# nahhhhh.net
KiCad netlist of a schematic drawn in EAGLE
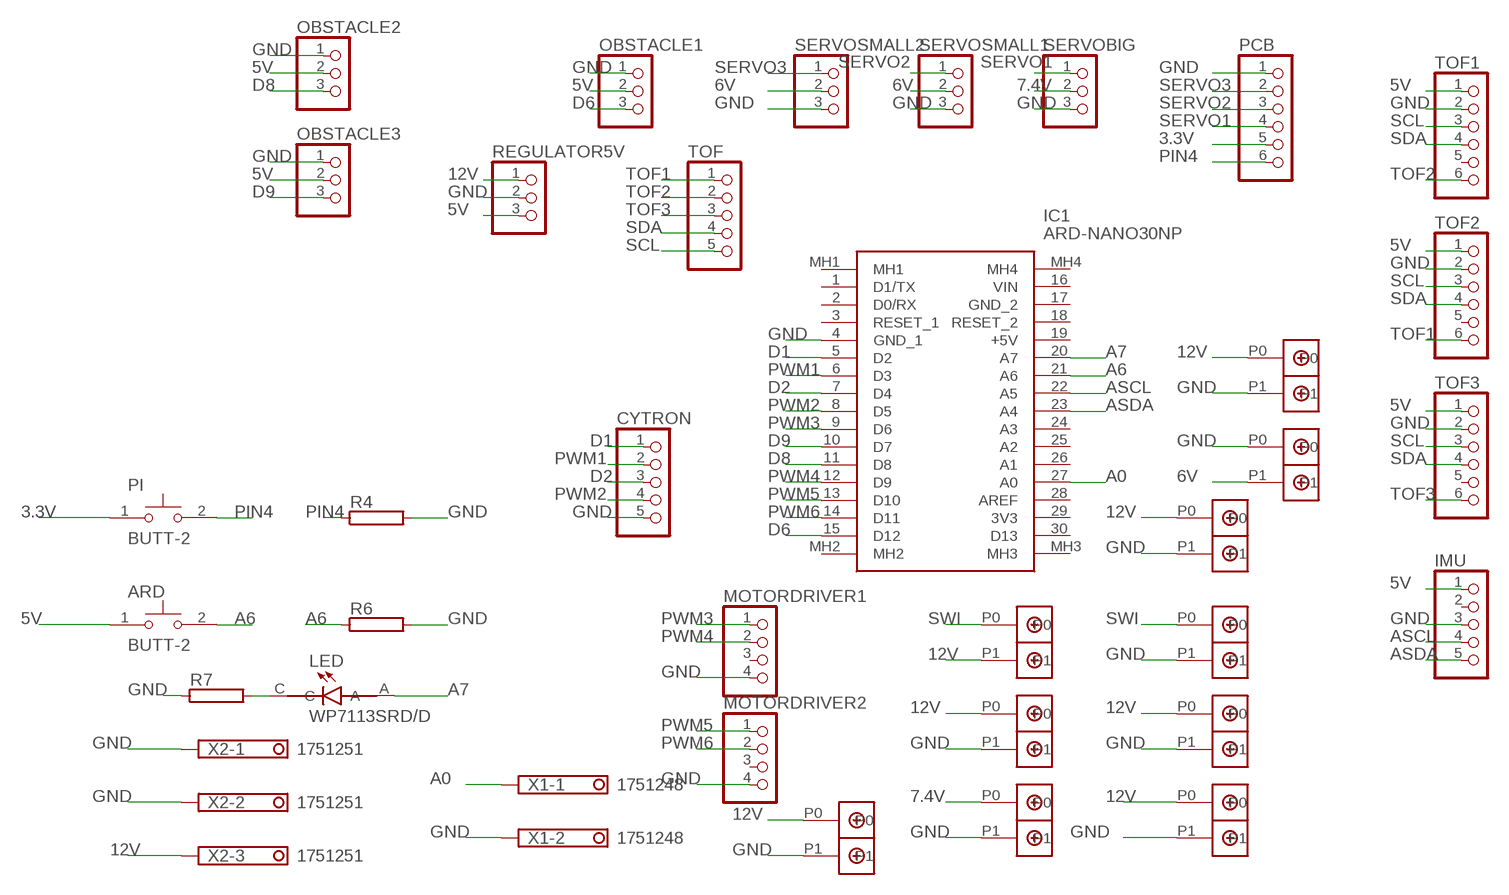
[diagram p0: schematic, sheet 1]

(export (version "E")
  (design (tool "Eeschema 10.0.6"))
  (components
    (comp (ref "ARD")
      (value "BUTT-2")
      (footprint "eagle-import:SW_BUTT-2")
      (fields (field (name "MF") "Gravitech"))
      (libsource (lib "eagle-import") (part "BUTT-2"))
    )
    (comp (ref "BATERY")
      (value "DBCONN-1X2")
      (footprint "eagle-import:DBCONN-1X2")
      (libsource (lib "eagle-import") (part "DBCONN-1X2"))
    )
    (comp (ref "BUCKSERVO")
      (value "DBCONN-1X2")
      (footprint "eagle-import:DBCONN-1X2")
      (libsource (lib "eagle-import") (part "DBCONN-1X2"))
    )
    (comp (ref "CYTRON")
      (value "PINHD-1X5")
      (footprint "eagle-import:1X05")
      (libsource (lib "eagle-import") (part "PINHD-1X5"))
    )
    (comp (ref "CYTRONPOWER")
      (value "DBCONN-1X2")
      (footprint "eagle-import:DBCONN-1X2")
      (libsource (lib "eagle-import") (part "DBCONN-1X2"))
    )
    (comp (ref "IC1")
      (value "ARD-NANO30NP")
      (footprint "eagle-import:ARDNANO30NP")
      (fields (field (name "MOUSER_PART_NUMBER") "992-ARD-NANO30NP"))
      (libsource (lib "eagle-import") (part "ARD-NANO30NP"))
    )
    (comp (ref "IMU")
      (value "PINHD-1X5")
      (footprint "eagle-import:1X05")
      (libsource (lib "eagle-import") (part "PINHD-1X5"))
    )
    (comp (ref "LED")
      (value "WP7113SRD/D")
      (footprint "eagle-import:LED_WP7113SRD_D")
      (fields (field (name "MF") "Kingbright"))
      (libsource (lib "eagle-import") (part "WP7113SRD/D"))
    )
    (comp (ref "LEDS")
      (value "DBCONN-1X2")
      (footprint "eagle-import:DBCONN-1X2")
      (libsource (lib "eagle-import") (part "DBCONN-1X2"))
    )
    (comp (ref "LEDS1")
      (value "DBCONN-1X2")
      (footprint "eagle-import:DBCONN-1X2")
      (libsource (lib "eagle-import") (part "DBCONN-1X2"))
    )
    (comp (ref "LEDS2")
      (value "DBCONN-1X2")
      (footprint "eagle-import:DBCONN-1X2")
      (libsource (lib "eagle-import") (part "DBCONN-1X2"))
    )
    (comp (ref "LEDS3")
      (value "DBCONN-1X2")
      (footprint "eagle-import:DBCONN-1X2")
      (libsource (lib "eagle-import") (part "DBCONN-1X2"))
    )
    (comp (ref "LEDS4")
      (value "DBCONN-1X2")
      (footprint "eagle-import:DBCONN-1X2")
      (libsource (lib "eagle-import") (part "DBCONN-1X2"))
    )
    (comp (ref "LEDS5")
      (value "DBCONN-1X2")
      (footprint "eagle-import:DBCONN-1X2")
      (libsource (lib "eagle-import") (part "DBCONN-1X2"))
    )
    (comp (ref "MOTORDRIVER1")
      (value "PINHD-1X4")
      (footprint "eagle-import:1X04")
      (libsource (lib "eagle-import") (part "PINHD-1X4"))
    )
    (comp (ref "MOTORDRIVER2")
      (value "PINHD-1X4")
      (footprint "eagle-import:1X04")
      (libsource (lib "eagle-import") (part "PINHD-1X4"))
    )
    (comp (ref "OBSTACLE1")
      (value "PINHD-1X3")
      (footprint "eagle-import:1X03")
      (libsource (lib "eagle-import") (part "PINHD-1X3"))
    )
    (comp (ref "OBSTACLE2")
      (value "PINHD-1X3")
      (footprint "eagle-import:1X03")
      (libsource (lib "eagle-import") (part "PINHD-1X3"))
    )
    (comp (ref "OBSTACLE3")
      (value "PINHD-1X3")
      (footprint "eagle-import:1X03")
      (libsource (lib "eagle-import") (part "PINHD-1X3"))
    )
    (comp (ref "PCB")
      (value "PINHD-1X6")
      (footprint "eagle-import:1X06")
      (libsource (lib "eagle-import") (part "PINHD-1X6"))
    )
    (comp (ref "PI")
      (value "BUTT-2")
      (footprint "eagle-import:SW_BUTT-2")
      (fields (field (name "MF") "Gravitech"))
      (libsource (lib "eagle-import") (part "BUTT-2"))
    )
    (comp (ref "R4")
      (value "RHPS58")
      (footprint "eagle-import:HPS58")
      (libsource (lib "eagle-import") (part "RHPS58"))
    )
    (comp (ref "R6")
      (value "RHPS58")
      (footprint "eagle-import:HPS58")
      (libsource (lib "eagle-import") (part "RHPS58"))
    )
    (comp (ref "R7")
      (value "RHPS58")
      (footprint "eagle-import:HPS58")
      (libsource (lib "eagle-import") (part "RHPS58"))
    )
    (comp (ref "REGULATOR5V")
      (value "PINHD-1X3")
      (footprint "eagle-import:1X03")
      (libsource (lib "eagle-import") (part "PINHD-1X3"))
    )
    (comp (ref "SERVOBIG")
      (value "PINHD-1X3")
      (footprint "eagle-import:1X03")
      (libsource (lib "eagle-import") (part "PINHD-1X3"))
    )
    (comp (ref "SERVOSMALL1")
      (value "PINHD-1X3")
      (footprint "eagle-import:1X03")
      (libsource (lib "eagle-import") (part "PINHD-1X3"))
    )
    (comp (ref "SERVOSMALL2")
      (value "PINHD-1X3")
      (footprint "eagle-import:1X03")
      (libsource (lib "eagle-import") (part "PINHD-1X3"))
    )
    (comp (ref "TOF")
      (value "PINHD-1X5")
      (footprint "eagle-import:1X05")
      (libsource (lib "eagle-import") (part "PINHD-1X5"))
    )
    (comp (ref "TOF1")
      (value "PINHD-1X6")
      (footprint "eagle-import:1X06")
      (libsource (lib "eagle-import") (part "PINHD-1X6"))
    )
    (comp (ref "TOF2")
      (value "PINHD-1X6")
      (footprint "eagle-import:1X06")
      (libsource (lib "eagle-import") (part "PINHD-1X6"))
    )
    (comp (ref "TOF3")
      (value "PINHD-1X6")
      (footprint "eagle-import:1X06")
      (libsource (lib "eagle-import") (part "PINHD-1X6"))
    )
    (comp (ref "U$1")
      (value "DBCONN-1X2")
      (footprint "eagle-import:DBCONN-1X2")
      (libsource (lib "eagle-import") (part "DBCONN-1X2"))
    )
    (comp (ref "X1")
      (value "1751248")
      (footprint "eagle-import:1751248")
      (libsource (lib "eagle-import") (part "1751248"))
    )
    (comp (ref "X2")
      (value "1751251")
      (footprint "eagle-import:1751251")
      (libsource (lib "eagle-import") (part "1751251"))
    )
  )
  (nets
    (net (code "1") (name "/3.3V") (class "Default")
      (node (ref "PCB") (pin "5") (pinfunction "5_5") (pintype "passive"))
      (node (ref "PI") (pin "1") (pinfunction "1_1") (pintype "passive"))
    )
    (net (code "2") (name "/5V") (class "Default")
      (node (ref "ARD") (pin "1") (pinfunction "1_1") (pintype "passive"))
      (node (ref "IMU") (pin "1") (pinfunction "1_1") (pintype "passive"))
      (node (ref "OBSTACLE1") (pin "2") (pinfunction "2_2") (pintype "passive"))
      (node (ref "OBSTACLE2") (pin "2") (pinfunction "2_2") (pintype "passive"))
      (node (ref "OBSTACLE3") (pin "2") (pinfunction "2_2") (pintype "passive"))
      (node (ref "REGULATOR5V") (pin "3") (pinfunction "3_3") (pintype "passive"))
      (node (ref "TOF1") (pin "1") (pinfunction "1_1") (pintype "passive"))
      (node (ref "TOF2") (pin "1") (pinfunction "1_1") (pintype "passive"))
      (node (ref "TOF3") (pin "1") (pinfunction "1_1") (pintype "passive"))
    )
    (net (code "3") (name "/6V") (class "Default")
      (node (ref "LEDS5") (pin "P1") (pinfunction "P1_P1") (pintype "bidirectional"))
      (node (ref "SERVOSMALL1") (pin "2") (pinfunction "2_2") (pintype "passive"))
      (node (ref "SERVOSMALL2") (pin "2") (pinfunction "2_2") (pintype "passive"))
    )
    (net (code "4") (name "/7.4V") (class "Default")
      (node (ref "SERVOBIG") (pin "2") (pinfunction "2_2") (pintype "passive"))
      (node (ref "U$1") (pin "P0") (pinfunction "P0_P0") (pintype "bidirectional"))
    )
    (net (code "5") (name "/12V") (class "Default")
      (node (ref "BUCKSERVO") (pin "P0") (pinfunction "P0_P0") (pintype "bidirectional"))
      (node (ref "CYTRONPOWER") (pin "P0") (pinfunction "P0_P0") (pintype "bidirectional"))
      (node (ref "LEDS") (pin "P0") (pinfunction "P0_P0") (pintype "bidirectional"))
      (node (ref "LEDS1") (pin "P1") (pinfunction "P1_P1") (pintype "bidirectional"))
      (node (ref "LEDS2") (pin "P0") (pinfunction "P0_P0") (pintype "bidirectional"))
      (node (ref "LEDS3") (pin "P0") (pinfunction "P0_P0") (pintype "bidirectional"))
      (node (ref "LEDS4") (pin "P0") (pinfunction "P0_P0") (pintype "bidirectional"))
      (node (ref "REGULATOR5V") (pin "1") (pinfunction "1_1") (pintype "passive"))
      (node (ref "X2") (pin "3") (pinfunction "K_3") (pintype "passive"))
    )
    (net (code "6") (name "/A0") (class "Default")
      (node (ref "IC1") (pin "27") (pinfunction "A0_27") (pintype "bidirectional"))
      (node (ref "X1") (pin "1") (pinfunction "K_1") (pintype "passive"))
    )
    (net (code "7") (name "/A6") (class "Default")
      (node (ref "ARD") (pin "2") (pinfunction "2_2") (pintype "passive"))
      (node (ref "IC1") (pin "21") (pinfunction "A6_21") (pintype "bidirectional"))
      (node (ref "R6") (pin "1") (pinfunction "1_1") (pintype "passive"))
    )
    (net (code "8") (name "/A7") (class "Default")
      (node (ref "IC1") (pin "20") (pinfunction "A7_20") (pintype "bidirectional"))
      (node (ref "LED") (pin "A") (pinfunction "A_A") (pintype "passive"))
    )
    (net (code "9") (name "/ASCL") (class "Default")
      (node (ref "IC1") (pin "22") (pinfunction "A5_22") (pintype "bidirectional"))
      (node (ref "IMU") (pin "4") (pinfunction "4_4") (pintype "passive"))
    )
    (net (code "10") (name "/ASDA") (class "Default")
      (node (ref "IC1") (pin "23") (pinfunction "A4_23") (pintype "bidirectional"))
      (node (ref "IMU") (pin "5") (pinfunction "5_5") (pintype "passive"))
    )
    (net (code "11") (name "/D1") (class "Default")
      (node (ref "CYTRON") (pin "1") (pinfunction "1_1") (pintype "passive"))
      (node (ref "IC1") (pin "5") (pinfunction "D2_5") (pintype "bidirectional"))
    )
    (net (code "12") (name "/D2") (class "Default")
      (node (ref "CYTRON") (pin "3") (pinfunction "3_3") (pintype "passive"))
      (node (ref "IC1") (pin "7") (pinfunction "D4_7") (pintype "bidirectional"))
    )
    (net (code "13") (name "/D6") (class "Default")
      (node (ref "IC1") (pin "15") (pinfunction "D12_15") (pintype "bidirectional"))
      (node (ref "OBSTACLE1") (pin "3") (pinfunction "3_3") (pintype "passive"))
    )
    (net (code "14") (name "/D8") (class "Default")
      (node (ref "IC1") (pin "11") (pinfunction "D8_11") (pintype "bidirectional"))
      (node (ref "OBSTACLE2") (pin "3") (pinfunction "3_3") (pintype "passive"))
    )
    (net (code "15") (name "/D9") (class "Default")
      (node (ref "IC1") (pin "10") (pinfunction "D7_10") (pintype "bidirectional"))
      (node (ref "OBSTACLE3") (pin "3") (pinfunction "3_3") (pintype "passive"))
    )
    (net (code "16") (name "/GND") (class "Default")
      (node (ref "BATERY") (pin "P1") (pinfunction "P1_P1") (pintype "bidirectional"))
      (node (ref "BUCKSERVO") (pin "P1") (pinfunction "P1_P1") (pintype "bidirectional"))
      (node (ref "CYTRON") (pin "5") (pinfunction "5_5") (pintype "passive"))
      (node (ref "CYTRONPOWER") (pin "P1") (pinfunction "P1_P1") (pintype "bidirectional"))
      (node (ref "IC1") (pin "4") (pinfunction "GND_1_4") (pintype "bidirectional"))
      (node (ref "IMU") (pin "3") (pinfunction "3_3") (pintype "passive"))
      (node (ref "LEDS") (pin "P1") (pinfunction "P1_P1") (pintype "bidirectional"))
      (node (ref "LEDS2") (pin "P1") (pinfunction "P1_P1") (pintype "bidirectional"))
      (node (ref "LEDS3") (pin "P1") (pinfunction "P1_P1") (pintype "bidirectional"))
      (node (ref "LEDS4") (pin "P1") (pinfunction "P1_P1") (pintype "bidirectional"))
      (node (ref "LEDS5") (pin "P0") (pinfunction "P0_P0") (pintype "bidirectional"))
      (node (ref "MOTORDRIVER1") (pin "4") (pinfunction "4_4") (pintype "passive"))
      (node (ref "MOTORDRIVER2") (pin "4") (pinfunction "4_4") (pintype "passive"))
      (node (ref "OBSTACLE1") (pin "1") (pinfunction "1_1") (pintype "passive"))
      (node (ref "OBSTACLE2") (pin "1") (pinfunction "1_1") (pintype "passive"))
      (node (ref "OBSTACLE3") (pin "1") (pinfunction "1_1") (pintype "passive"))
      (node (ref "PCB") (pin "1") (pinfunction "1_1") (pintype "passive"))
      (node (ref "R4") (pin "2") (pinfunction "2_2") (pintype "passive"))
      (node (ref "R6") (pin "2") (pinfunction "2_2") (pintype "passive"))
      (node (ref "R7") (pin "1") (pinfunction "1_1") (pintype "passive"))
      (node (ref "REGULATOR5V") (pin "2") (pinfunction "2_2") (pintype "passive"))
      (node (ref "SERVOBIG") (pin "3") (pinfunction "3_3") (pintype "passive"))
      (node (ref "SERVOSMALL1") (pin "3") (pinfunction "3_3") (pintype "passive"))
      (node (ref "SERVOSMALL2") (pin "3") (pinfunction "3_3") (pintype "passive"))
      (node (ref "TOF1") (pin "2") (pinfunction "2_2") (pintype "passive"))
      (node (ref "TOF2") (pin "2") (pinfunction "2_2") (pintype "passive"))
      (node (ref "TOF3") (pin "2") (pinfunction "2_2") (pintype "passive"))
      (node (ref "U$1") (pin "P1") (pinfunction "P1_P1") (pintype "bidirectional"))
      (node (ref "X1") (pin "2") (pinfunction "K_2") (pintype "passive"))
      (node (ref "X2") (pin "1") (pinfunction "K_1") (pintype "passive"))
      (node (ref "X2") (pin "2") (pinfunction "K_2") (pintype "passive"))
    )
    (net (code "17") (name "/PIN4") (class "Default")
      (node (ref "PCB") (pin "6") (pinfunction "6_6") (pintype "passive"))
      (node (ref "PI") (pin "2") (pinfunction "2_2") (pintype "passive"))
      (node (ref "R4") (pin "1") (pinfunction "1_1") (pintype "passive"))
    )
    (net (code "18") (name "/PWM1") (class "Default")
      (node (ref "CYTRON") (pin "2") (pinfunction "2_2") (pintype "passive"))
      (node (ref "IC1") (pin "6") (pinfunction "D3_6") (pintype "bidirectional"))
    )
    (net (code "19") (name "/PWM2") (class "Default")
      (node (ref "CYTRON") (pin "4") (pinfunction "4_4") (pintype "passive"))
      (node (ref "IC1") (pin "8") (pinfunction "D5_8") (pintype "bidirectional"))
    )
    (net (code "20") (name "/PWM3") (class "Default")
      (node (ref "IC1") (pin "9") (pinfunction "D6_9") (pintype "bidirectional"))
      (node (ref "MOTORDRIVER1") (pin "1") (pinfunction "1_1") (pintype "passive"))
    )
    (net (code "21") (name "/PWM4") (class "Default")
      (node (ref "IC1") (pin "12") (pinfunction "D9_12") (pintype "bidirectional"))
      (node (ref "MOTORDRIVER1") (pin "2") (pinfunction "2_2") (pintype "passive"))
    )
    (net (code "22") (name "/PWM5") (class "Default")
      (node (ref "IC1") (pin "13") (pinfunction "D10_13") (pintype "bidirectional"))
      (node (ref "MOTORDRIVER2") (pin "1") (pinfunction "1_1") (pintype "passive"))
    )
    (net (code "23") (name "/PWM6") (class "Default")
      (node (ref "IC1") (pin "14") (pinfunction "D11_14") (pintype "bidirectional"))
      (node (ref "MOTORDRIVER2") (pin "2") (pinfunction "2_2") (pintype "passive"))
    )
    (net (code "24") (name "/SCL") (class "Default")
      (node (ref "TOF") (pin "5") (pinfunction "5_5") (pintype "passive"))
      (node (ref "TOF1") (pin "3") (pinfunction "3_3") (pintype "passive"))
      (node (ref "TOF2") (pin "3") (pinfunction "3_3") (pintype "passive"))
      (node (ref "TOF3") (pin "3") (pinfunction "3_3") (pintype "passive"))
    )
    (net (code "25") (name "/SDA") (class "Default")
      (node (ref "TOF") (pin "4") (pinfunction "4_4") (pintype "passive"))
      (node (ref "TOF1") (pin "4") (pinfunction "4_4") (pintype "passive"))
      (node (ref "TOF2") (pin "4") (pinfunction "4_4") (pintype "passive"))
      (node (ref "TOF3") (pin "4") (pinfunction "4_4") (pintype "passive"))
    )
    (net (code "26") (name "/SERVO1") (class "Default")
      (node (ref "PCB") (pin "4") (pinfunction "4_4") (pintype "passive"))
      (node (ref "SERVOBIG") (pin "1") (pinfunction "1_1") (pintype "passive"))
    )
    (net (code "27") (name "/SERVO2") (class "Default")
      (node (ref "PCB") (pin "3") (pinfunction "3_3") (pintype "passive"))
      (node (ref "SERVOSMALL1") (pin "1") (pinfunction "1_1") (pintype "passive"))
    )
    (net (code "28") (name "/SERVO3") (class "Default")
      (node (ref "PCB") (pin "2") (pinfunction "2_2") (pintype "passive"))
      (node (ref "SERVOSMALL2") (pin "1") (pinfunction "1_1") (pintype "passive"))
    )
    (net (code "29") (name "/SWI") (class "Default")
      (node (ref "BATERY") (pin "P0") (pinfunction "P0_P0") (pintype "bidirectional"))
      (node (ref "LEDS1") (pin "P0") (pinfunction "P0_P0") (pintype "bidirectional"))
    )
    (net (code "30") (name "/TOF1") (class "Default")
      (node (ref "TOF") (pin "1") (pinfunction "1_1") (pintype "passive"))
      (node (ref "TOF2") (pin "6") (pinfunction "6_6") (pintype "passive"))
    )
    (net (code "31") (name "/TOF2") (class "Default")
      (node (ref "TOF") (pin "2") (pinfunction "2_2") (pintype "passive"))
      (node (ref "TOF1") (pin "6") (pinfunction "6_6") (pintype "passive"))
    )
    (net (code "32") (name "/TOF3") (class "Default")
      (node (ref "TOF") (pin "3") (pinfunction "3_3") (pintype "passive"))
      (node (ref "TOF3") (pin "6") (pinfunction "6_6") (pintype "passive"))
    )
    (net (code "33") (name "Net-(LED-PadC)") (class "Default")
      (node (ref "LED") (pin "C") (pinfunction "C_C") (pintype "passive"))
      (node (ref "R7") (pin "2") (pinfunction "2_2") (pintype "passive"))
    )
    (net (code "34") (name "unconnected-(IC1-+5V-Pad19)") (class "Default")
      (node (ref "IC1") (pin "19") (pinfunction "+5V_19") (pintype "bidirectional"))
    )
    (net (code "35") (name "unconnected-(IC1-3V3-Pad29)") (class "Default")
      (node (ref "IC1") (pin "29") (pinfunction "3V3_29") (pintype "bidirectional"))
    )
    (net (code "36") (name "unconnected-(IC1-A1-Pad26)") (class "Default")
      (node (ref "IC1") (pin "26") (pinfunction "A1_26") (pintype "bidirectional"))
    )
    (net (code "37") (name "unconnected-(IC1-A2-Pad25)") (class "Default")
      (node (ref "IC1") (pin "25") (pinfunction "A2_25") (pintype "bidirectional"))
    )
    (net (code "38") (name "unconnected-(IC1-A3-Pad24)") (class "Default")
      (node (ref "IC1") (pin "24") (pinfunction "A3_24") (pintype "bidirectional"))
    )
    (net (code "39") (name "unconnected-(IC1-AREF-Pad28)") (class "Default")
      (node (ref "IC1") (pin "28") (pinfunction "AREF_28") (pintype "bidirectional"))
    )
    (net (code "40") (name "unconnected-(IC1-D0{slash}RX-Pad2)") (class "Default")
      (node (ref "IC1") (pin "2") (pinfunction "D0/RX_2") (pintype "bidirectional"))
    )
    (net (code "41") (name "unconnected-(IC1-D1{slash}TX-Pad1)") (class "Default")
      (node (ref "IC1") (pin "1") (pinfunction "D1/TX_1") (pintype "bidirectional"))
    )
    (net (code "42") (name "unconnected-(IC1-D13-Pad30)") (class "Default")
      (node (ref "IC1") (pin "30") (pinfunction "D13_30") (pintype "bidirectional"))
    )
    (net (code "43") (name "unconnected-(IC1-GND_2-Pad17)") (class "Default")
      (node (ref "IC1") (pin "17") (pinfunction "GND_2_17") (pintype "bidirectional"))
    )
    (net (code "44") (name "unconnected-(IC1-PadMH1)") (class "Default")
      (node (ref "IC1") (pin "MH1") (pinfunction "MH1_MH1") (pintype "bidirectional"))
    )
    (net (code "45") (name "unconnected-(IC1-PadMH2)") (class "Default")
      (node (ref "IC1") (pin "MH2") (pinfunction "MH2_MH2") (pintype "bidirectional"))
    )
    (net (code "46") (name "unconnected-(IC1-PadMH3)") (class "Default")
      (node (ref "IC1") (pin "MH3") (pinfunction "MH3_MH3") (pintype "bidirectional"))
    )
    (net (code "47") (name "unconnected-(IC1-PadMH4)") (class "Default")
      (node (ref "IC1") (pin "MH4") (pinfunction "MH4_MH4") (pintype "bidirectional"))
    )
    (net (code "48") (name "unconnected-(IC1-RESET_1-Pad3)") (class "Default")
      (node (ref "IC1") (pin "3") (pinfunction "RESET_1_3") (pintype "bidirectional"))
    )
    (net (code "49") (name "unconnected-(IC1-RESET_2-Pad18)") (class "Default")
      (node (ref "IC1") (pin "18") (pinfunction "RESET_2_18") (pintype "bidirectional"))
    )
    (net (code "50") (name "unconnected-(IC1-VIN-Pad16)") (class "Default")
      (node (ref "IC1") (pin "16") (pinfunction "VIN_16") (pintype "bidirectional"))
    )
    (net (code "51") (name "unconnected-(IMU-Pad2)") (class "Default")
      (node (ref "IMU") (pin "2") (pinfunction "2_2") (pintype "passive"))
    )
    (net (code "52") (name "unconnected-(MOTORDRIVER1-Pad3)") (class "Default")
      (node (ref "MOTORDRIVER1") (pin "3") (pinfunction "3_3") (pintype "passive"))
    )
    (net (code "53") (name "unconnected-(MOTORDRIVER2-Pad3)") (class "Default")
      (node (ref "MOTORDRIVER2") (pin "3") (pinfunction "3_3") (pintype "passive"))
    )
    (net (code "54") (name "unconnected-(TOF1-Pad5)") (class "Default")
      (node (ref "TOF1") (pin "5") (pinfunction "5_5") (pintype "passive"))
    )
    (net (code "55") (name "unconnected-(TOF2-Pad5)") (class "Default")
      (node (ref "TOF2") (pin "5") (pinfunction "5_5") (pintype "passive"))
    )
    (net (code "56") (name "unconnected-(TOF3-Pad5)") (class "Default")
      (node (ref "TOF3") (pin "5") (pinfunction "5_5") (pintype "passive"))
    )
  )
)
